# Reference_2V5.net
KiCad netlist of a schematic drawn in Altium Designer
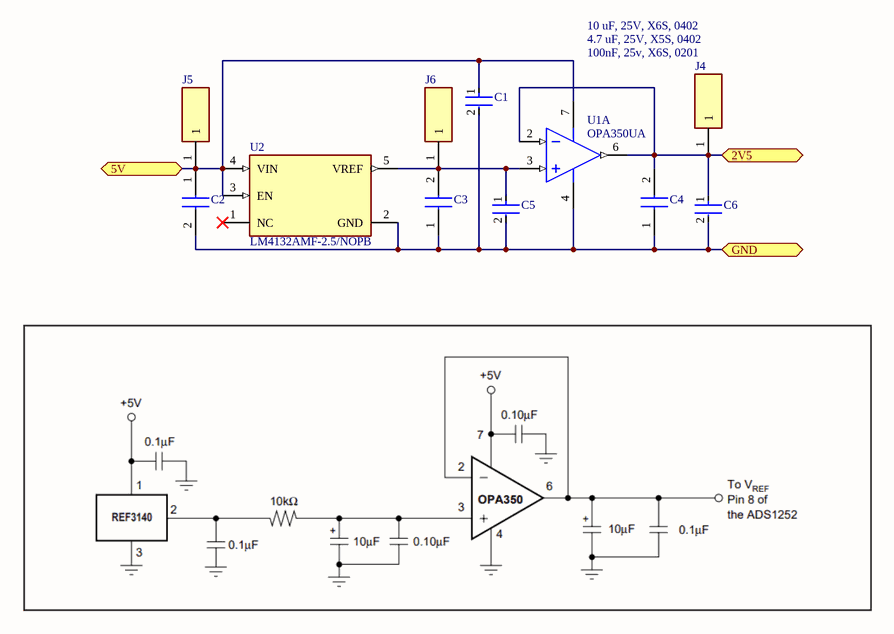
[diagram p0: Reference_2V5.SchDoc]

(export (version "E")
  (design (tool "Eeschema 10.0.6"))
  (components
    (comp (ref "C1")
      (value "100nF, 25v, X6S, 0201")
      (footprint "FP-GRM033-0_03-IPC_B")
      (description "Chip Multilayer Ceramic Capacitors for General Purpose, 0201, 0.10uF, X6S, 22%, 10%, 25V")
      (fields (field (name "TOLERANCE") "10%"))
      (libsource (lib "Altium Content Vault") (part "b4654b650e69147ec39a6b967a45e02"))
    )
    (comp (ref "C2")
      (value "10 uF, 25V, X6S, 0402")
      (footprint "SamacSys:CAPC1005X70N")
      (description "Capacitor")
      (fields
        (field (name "MANUFACTURER_PART_NUMBER") "GRM155F51E104ZA01E")
        (field (name "MOUSER PART NUMBER") "81-GRM15F51E104ZA01E")
      )
      (libsource (lib "*") (part "GRM155F51E104ZA01E"))
    )
    (comp (ref "C3")
      (value "4.7 uF, 25V, X5S, 0402")
      (footprint "SamacSys:GRM15x")
      (description "Capacitor")
      (fields
        (field (name "MANUFACTURER_PART_NUMBER") "GRM155C61E475ME15J")
        (field (name "MOUSER PART NUMBER") "81-GRM15C61E475ME15J")
      )
      (libsource (lib "*") (part "GRM155C61E475ME15J"))
    )
    (comp (ref "C4")
      (value "10 uF, 25V, X6S, 0402")
      (footprint "SamacSys:CAPC1005X70N")
      (description "Capacitor")
      (fields
        (field (name "MANUFACTURER_PART_NUMBER") "GRM155F51E104ZA01E")
        (field (name "MOUSER PART NUMBER") "81-GRM15F51E104ZA01E")
      )
      (libsource (lib "*") (part "GRM155F51E104ZA01E"))
    )
    (comp (ref "C5")
      (value "100nF, 25v, X6S, 0201")
      (footprint "FP-GRM033-0_03-IPC_B")
      (description "Chip Multilayer Ceramic Capacitors for General Purpose, 0201, 0.10uF, X6S, 22%, 10%, 25V")
      (fields (field (name "TOLERANCE") "10%"))
      (libsource (lib "Altium Content Vault") (part "b4654b650e69147ec39a6b967a45e02"))
    )
    (comp (ref "C6")
      (value "100nF, 25v, X6S, 0201")
      (footprint "FP-GRM033-0_03-IPC_B")
      (description "Chip Multilayer Ceramic Capacitors for General Purpose, 0201, 0.10uF, X6S, 22%, 10%, 25V")
      (fields (field (name "TOLERANCE") "10%"))
      (libsource (lib "Altium Content Vault") (part "b4654b650e69147ec39a6b967a45e02"))
    )
    (comp (ref "J4")
      (value "TestPad")
      (footprint "SamacSys:TestPad")
      (description "Connector")
      (fields
        (field (name "MANUFACTURER_PART_NUMBER") "61300111121")
        (field (name "MOUSER PART NUMBER") "710-61300111121")
      )
      (libsource (lib "*") (part "61300111121"))
    )
    (comp (ref "J5")
      (value "TestPad")
      (footprint "SamacSys:TestPad")
      (description "Connector")
      (fields
        (field (name "MANUFACTURER_PART_NUMBER") "61300111121")
        (field (name "MOUSER PART NUMBER") "710-61300111121")
      )
      (libsource (lib "") (part "61300111121_1"))
    )
    (comp (ref "J6")
      (value "TestPad")
      (footprint "SamacSys:TestPad")
      (description "Connector")
      (fields
        (field (name "MANUFACTURER_PART_NUMBER") "61300111121")
        (field (name "MOUSER PART NUMBER") "710-61300111121")
      )
      (libsource (lib "") (part "61300111121_1"))
    )
    (comp (ref "U1")
      (value "OPA350UA")
      (footprint "D0008A_M")
      (fields (field (name "MANUFACTURER") "Texas Instruments"))
      (libsource (lib "Altium Content Vault") (part "TI-OPA-8_1"))
    )
    (comp (ref "U2")
      (value "LM4132AMF-2.5/NOPB")
      (footprint "FP-DBV0005A-IPC_C")
      (description "IC VREF SERIES 0.05% SOT23-5")
      (fields (field (name "TOLERANCE") "0.05%"))
      (libsource (lib "Altium Content Vault") (part "83a8c20666b8818ecf60699c622df6d"))
    )
  )
  (nets
    (net (code "1") (name "/2V5") (class "Default")
      (node (ref "C4") (pin "2") (pinfunction "2_2") (pintype "passive"))
      (node (ref "C6") (pin "1") (pinfunction "1_1") (pintype "passive"))
      (node (ref "J4") (pin "1") (pinfunction "1_1") (pintype "passive"))
      (node (ref "U1") (pin "2") (pinfunction "IN-_2") (pintype "input"))
      (node (ref "U1") (pin "6") (pinfunction "OUT_6") (pintype "output"))
    )
    (net (code "2") (name "/5V") (class "Default")
      (node (ref "C1") (pin "1") (pinfunction "1_1") (pintype "passive"))
      (node (ref "C2") (pin "1") (pinfunction "1_1") (pintype "passive"))
      (node (ref "J5") (pin "1") (pinfunction "1_1") (pintype "passive"))
      (node (ref "U1") (pin "7") (pinfunction "V+_7") (pintype "power_in"))
      (node (ref "U2") (pin "3") (pinfunction "EN_3") (pintype "input"))
      (node (ref "U2") (pin "4") (pinfunction "VIN_4") (pintype "input"))
    )
    (net (code "3") (name "/GND") (class "Default")
      (node (ref "C1") (pin "2") (pinfunction "2_2") (pintype "passive"))
      (node (ref "C2") (pin "2") (pinfunction "2_2") (pintype "passive"))
      (node (ref "C3") (pin "1") (pinfunction "1_1") (pintype "passive"))
      (node (ref "C4") (pin "1") (pinfunction "1_1") (pintype "passive"))
      (node (ref "C5") (pin "2") (pinfunction "2_2") (pintype "passive"))
      (node (ref "C6") (pin "2") (pinfunction "2_2") (pintype "passive"))
      (node (ref "U1") (pin "4") (pinfunction "V-_4") (pintype "power_in"))
      (node (ref "U2") (pin "2") (pinfunction "GND_2") (pintype "power_in"))
    )
    (net (code "4") (name "Net-(U1A-IN+)") (class "Default")
      (node (ref "C3") (pin "2") (pinfunction "2_2") (pintype "passive"))
      (node (ref "C5") (pin "1") (pinfunction "1_1") (pintype "passive"))
      (node (ref "J6") (pin "1") (pinfunction "1_1") (pintype "passive"))
      (node (ref "U1") (pin "3") (pinfunction "IN+_3") (pintype "input"))
      (node (ref "U2") (pin "5") (pinfunction "VREF_5") (pintype "output"))
    )
    (net (code "5") (name "unconnected-(U2-NC-Pad1)") (class "Default")
      (node (ref "U2") (pin "1") (pinfunction "NC_1") (pintype "passive+no_connect"))
    )
  )
)
